# mbed-enablement-platform_F_1.net
KiCad netlist of a schematic drawn in Altium Designer
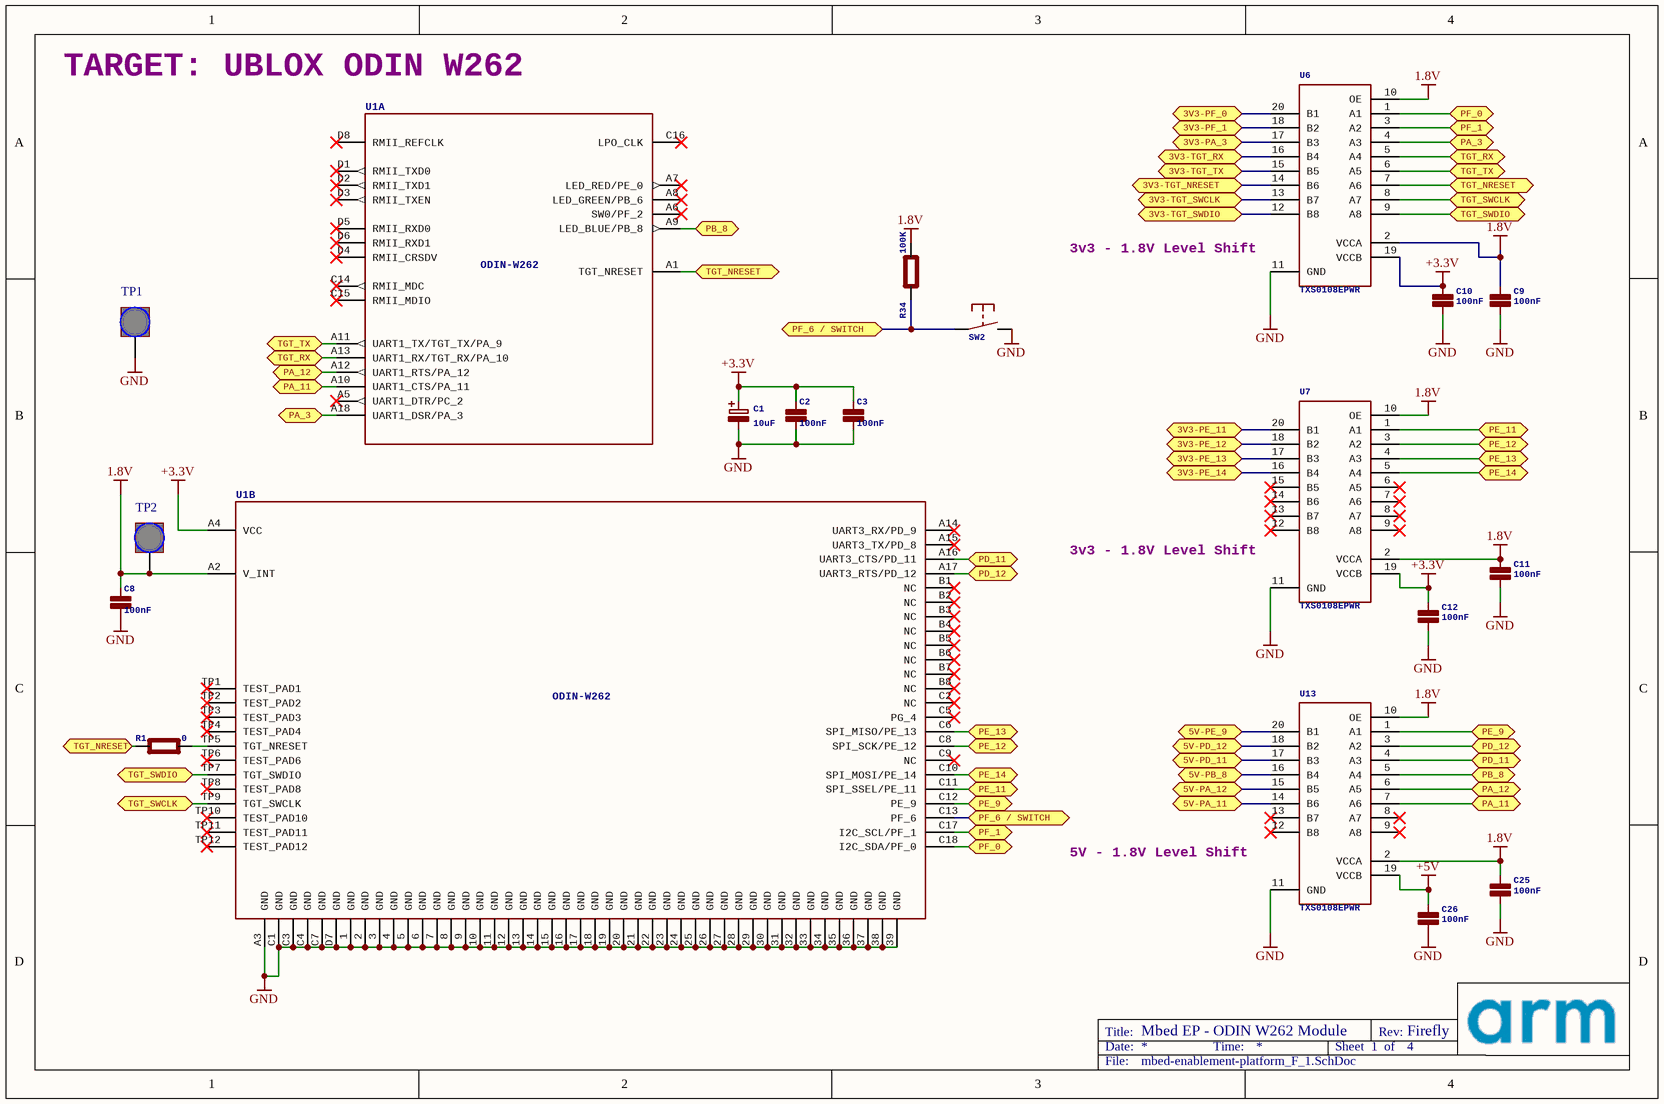
[diagram p0: mbed-enablement-platform_F_1.SchDoc]

(export (version "E")
  (design (tool "Eeschema 10.0.6"))
  (components
    (comp (ref "C1")
      (value "10uF")
      (footprint "SMC_B")
      (description "Polarised capacitor")
      (fields (field (name "MF") "Kemet"))
      (libsource (lib "mbed-workplace-env-mon") (part "CAPACITOR-POLARISEDB"))
    )
    (comp (ref "C2")
      (value "100nF")
      (footprint "0603")
      (description "Capacitor")
      (libsource (lib "mbed-workplace-env-mon") (part "CAPACITOR0603"))
    )
    (comp (ref "C3")
      (value "100nF")
      (footprint "0603")
      (description "Capacitor")
      (libsource (lib "mbed-workplace-env-mon") (part "CAPACITOR0603"))
    )
    (comp (ref "C8")
      (value "100nF")
      (footprint "0603")
      (description "Capacitor")
      (libsource (lib "mbed-workplace-env-mon") (part "CAPACITOR0603"))
    )
    (comp (ref "C9")
      (value "100nF")
      (footprint "0603")
      (description "Capacitor")
      (libsource (lib "mbed-workplace-env-mon") (part "CAPACITOR0603"))
    )
    (comp (ref "C10")
      (value "100nF")
      (footprint "0603")
      (description "Capacitor")
      (libsource (lib "mbed-workplace-env-mon") (part "CAPACITOR0603"))
    )
    (comp (ref "C11")
      (value "100nF")
      (footprint "0603")
      (description "Capacitor")
      (libsource (lib "mbed-workplace-env-mon") (part "CAPACITOR0603"))
    )
    (comp (ref "C12")
      (value "100nF")
      (footprint "0603")
      (description "Capacitor")
      (libsource (lib "mbed-workplace-env-mon") (part "CAPACITOR0603"))
    )
    (comp (ref "C25")
      (value "100nF")
      (footprint "0603")
      (description "Capacitor")
      (libsource (lib "mbed-workplace-env-mon") (part "CAPACITOR0603"))
    )
    (comp (ref "C26")
      (value "100nF")
      (footprint "0603")
      (description "Capacitor")
      (libsource (lib "mbed-workplace-env-mon") (part "CAPACITOR0603"))
    )
    (comp (ref "R1")
      (value "0")
      (footprint "0402")
      (description "Resistor")
      (libsource (lib "mbed-workplace-env-mon") (part "RESISTOR0402"))
    )
    (comp (ref "R34")
      (value "100K")
      (footprint "0402")
      (description "Resistor")
      (libsource (lib "mbed-workplace-env-mon") (part "RESISTOR0402"))
    )
    (comp (ref "SW2")
      (value "MOMENTARY SWITCH RA (SPST)")
      (footprint "EVQ-PF006K")
      (description "EVQ-PF006K")
      (fields (field (name "MF") "Panasonic"))
      (libsource (lib "mbed-workplace-env-mon") (part "EVQ-PF006K"))
    )
    (comp (ref "TP1")
      (value "TP, 1.5mm")
      (footprint "TP1.5")
      (description "1.5mm round test point")
      (libsource (lib "mbed-workplace-env-mon") (part "TP1.5"))
    )
    (comp (ref "TP2")
      (value "TP, 1.5mm")
      (footprint "TP1.5")
      (description "1.5mm round test point")
      (libsource (lib "") (part "TP1.5_1"))
    )
    (comp (ref "U1")
      (value "ODIN-W262")
      (footprint "ODIN-88")
      (description "ODIN-W260: Host-based multiradio module with Wi-Fi and Bluetooth, internal antenna   u-blox.com")
      (libsource (lib "mbed-workplace-env-mon") (part "ODIN-W262"))
    )
    (comp (ref "U6")
      (value "TXS0108EPWR")
      (footprint "TSSOP-20")
      (description "8-Bit Bi-directional, Level-Shifting, Voltage Translator")
      (fields (field (name "MF") "Texas Instruments"))
      (libsource (lib "mbed-workplace-env-mon") (part "TXS0108EPWR"))
    )
    (comp (ref "U7")
      (value "TXS0108EPWR")
      (footprint "TSSOP-20")
      (description "8-Bit Bi-directional, Level-Shifting, Voltage Translator")
      (fields (field (name "MF") "Texas Instruments"))
      (libsource (lib "mbed-workplace-env-mon") (part "TXS0108EPWR"))
    )
    (comp (ref "U13")
      (value "TXS0108EPWR")
      (footprint "TSSOP-20")
      (description "8-Bit Bi-directional, Level-Shifting, Voltage Translator")
      (fields (field (name "MF") "Texas Instruments"))
      (libsource (lib "mbed-workplace-env-mon") (part "TXS0108EPWR"))
    )
  )
  (nets
    (net (code "1") (name "+3.3V") (class "Default")
      (node (ref "C1") (pin "+") (pinfunction "+_+") (pintype "passive"))
      (node (ref "C10") (pin "1") (pinfunction "P$1_1") (pintype "passive"))
      (node (ref "C12") (pin "1") (pinfunction "P$1_1") (pintype "passive"))
      (node (ref "C2") (pin "1") (pinfunction "P$1_1") (pintype "passive"))
      (node (ref "C3") (pin "1") (pinfunction "P$1_1") (pintype "passive"))
      (node (ref "U1") (pin "A4") (pinfunction "VCC_A4") (pintype "power_in"))
      (node (ref "U6") (pin "19") (pinfunction "VCCB_19") (pintype "passive"))
      (node (ref "U7") (pin "19") (pinfunction "VCCB_19") (pintype "passive"))
    )
    (net (code "2") (name "+5V") (class "Default")
      (node (ref "C26") (pin "1") (pinfunction "P$1_1") (pintype "passive"))
      (node (ref "U13") (pin "19") (pinfunction "VCCB_19") (pintype "passive"))
    )
    (net (code "3") (name "/3V3-PA_3") (class "Default")
      (node (ref "U6") (pin "17") (pinfunction "B3_17") (pintype "passive"))
    )
    (net (code "4") (name "/3V3-PE_11") (class "Default")
      (node (ref "U7") (pin "20") (pinfunction "B1_20") (pintype "passive"))
    )
    (net (code "5") (name "/3V3-PE_12") (class "Default")
      (node (ref "U7") (pin "18") (pinfunction "B2_18") (pintype "passive"))
    )
    (net (code "6") (name "/3V3-PE_13") (class "Default")
      (node (ref "U7") (pin "17") (pinfunction "B3_17") (pintype "passive"))
    )
    (net (code "7") (name "/3V3-PE_14") (class "Default")
      (node (ref "U7") (pin "16") (pinfunction "B4_16") (pintype "passive"))
    )
    (net (code "8") (name "/3V3-PF_0") (class "Default")
      (node (ref "U6") (pin "20") (pinfunction "B1_20") (pintype "passive"))
    )
    (net (code "9") (name "/3V3-PF_1") (class "Default")
      (node (ref "U6") (pin "18") (pinfunction "B2_18") (pintype "passive"))
    )
    (net (code "10") (name "/3V3-TGT_NRESET") (class "Default")
      (node (ref "U6") (pin "14") (pinfunction "B6_14") (pintype "passive"))
    )
    (net (code "11") (name "/3V3-TGT_RX") (class "Default")
      (node (ref "U6") (pin "16") (pinfunction "B4_16") (pintype "passive"))
    )
    (net (code "12") (name "/3V3-TGT_SWCLK") (class "Default")
      (node (ref "U6") (pin "13") (pinfunction "B7_13") (pintype "passive"))
    )
    (net (code "13") (name "/3V3-TGT_SWDIO") (class "Default")
      (node (ref "U6") (pin "12") (pinfunction "B8_12") (pintype "passive"))
    )
    (net (code "14") (name "/3V3-TGT_TX") (class "Default")
      (node (ref "U6") (pin "15") (pinfunction "B5_15") (pintype "passive"))
    )
    (net (code "15") (name "/5V-PA_11") (class "Default")
      (node (ref "U13") (pin "14") (pinfunction "B6_14") (pintype "passive"))
    )
    (net (code "16") (name "/5V-PA_12") (class "Default")
      (node (ref "U13") (pin "15") (pinfunction "B5_15") (pintype "passive"))
    )
    (net (code "17") (name "/5V-PB_8") (class "Default")
      (node (ref "U13") (pin "16") (pinfunction "B4_16") (pintype "passive"))
    )
    (net (code "18") (name "/5V-PD_11") (class "Default")
      (node (ref "U13") (pin "17") (pinfunction "B3_17") (pintype "passive"))
    )
    (net (code "19") (name "/5V-PD_12") (class "Default")
      (node (ref "U13") (pin "18") (pinfunction "B2_18") (pintype "passive"))
    )
    (net (code "20") (name "/5V-PE_9") (class "Default")
      (node (ref "U13") (pin "20") (pinfunction "B1_20") (pintype "passive"))
    )
    (net (code "21") (name "/PA_3") (class "Default")
      (node (ref "U1") (pin "A18") (pinfunction "UART1_DSR/PA_3_A18") (pintype "passive"))
      (node (ref "U6") (pin "4") (pinfunction "A3_4") (pintype "passive"))
    )
    (net (code "22") (name "/PA_11") (class "Default")
      (node (ref "U1") (pin "A10") (pinfunction "UART1_CTS/PA_11_A10") (pintype "passive"))
      (node (ref "U13") (pin "7") (pinfunction "A6_7") (pintype "passive"))
    )
    (net (code "23") (name "/PA_12") (class "Default")
      (node (ref "U1") (pin "A12") (pinfunction "UART1_RTS/PA_12_A12") (pintype "output"))
      (node (ref "U13") (pin "6") (pinfunction "A5_6") (pintype "passive"))
    )
    (net (code "24") (name "/PB_8") (class "Default")
      (node (ref "U1") (pin "A9") (pinfunction "LED_BLUE/PB_8_A9") (pintype "output"))
      (node (ref "U13") (pin "5") (pinfunction "A4_5") (pintype "passive"))
    )
    (net (code "25") (name "/PD_11") (class "Default")
      (node (ref "U1") (pin "A16") (pinfunction "UART3_CTS/PD_11_A16") (pintype "passive"))
      (node (ref "U13") (pin "4") (pinfunction "A3_4") (pintype "passive"))
    )
    (net (code "26") (name "/PD_12") (class "Default")
      (node (ref "U1") (pin "A17") (pinfunction "UART3_RTS/PD_12_A17") (pintype "passive"))
      (node (ref "U13") (pin "3") (pinfunction "A2_3") (pintype "passive"))
    )
    (net (code "27") (name "/PE_9") (class "Default")
      (node (ref "U1") (pin "C12") (pinfunction "PE_9_C12") (pintype "passive"))
      (node (ref "U13") (pin "1") (pinfunction "A1_1") (pintype "passive"))
    )
    (net (code "28") (name "/PE_11") (class "Default")
      (node (ref "U1") (pin "C11") (pinfunction "SPI_SSEL/PE_11_C11") (pintype "passive"))
      (node (ref "U7") (pin "1") (pinfunction "A1_1") (pintype "passive"))
    )
    (net (code "29") (name "/PE_12") (class "Default")
      (node (ref "U1") (pin "C8") (pinfunction "SPI_SCK/PE_12_C8") (pintype "passive"))
      (node (ref "U7") (pin "3") (pinfunction "A2_3") (pintype "passive"))
    )
    (net (code "30") (name "/PE_13") (class "Default")
      (node (ref "U1") (pin "C6") (pinfunction "SPI_MISO/PE_13_C6") (pintype "passive"))
      (node (ref "U7") (pin "4") (pinfunction "A3_4") (pintype "passive"))
    )
    (net (code "31") (name "/PE_14") (class "Default")
      (node (ref "U1") (pin "C10") (pinfunction "SPI_MOSI/PE_14_C10") (pintype "passive"))
      (node (ref "U7") (pin "5") (pinfunction "A4_5") (pintype "passive"))
    )
    (net (code "32") (name "/PF_0") (class "Default")
      (node (ref "U1") (pin "C18") (pinfunction "I2C_SDA/PF_0_C18") (pintype "passive"))
      (node (ref "U6") (pin "1") (pinfunction "A1_1") (pintype "passive"))
    )
    (net (code "33") (name "/PF_1") (class "Default")
      (node (ref "U1") (pin "C17") (pinfunction "I2C_SCL/PF_1_C17") (pintype "passive"))
      (node (ref "U6") (pin "3") (pinfunction "A2_3") (pintype "passive"))
    )
    (net (code "34") (name "/PF_6 {slash} SWITCH") (class "Default")
      (node (ref "R34") (pin "1") (pinfunction "P$1_1") (pintype "passive"))
      (node (ref "SW2") (pin "1") (pinfunction "1_1") (pintype "passive"))
      (node (ref "U1") (pin "C13") (pinfunction "PF_6_C13") (pintype "passive"))
    )
    (net (code "35") (name "/TGT_NRESET") (class "Default")
      (node (ref "R1") (pin "1") (pinfunction "P$1_1") (pintype "passive"))
      (node (ref "U1") (pin "A1") (pinfunction "TGT_NRESET_A1") (pintype "passive"))
      (node (ref "U6") (pin "7") (pinfunction "A6_7") (pintype "passive"))
    )
    (net (code "36") (name "/TGT_RX") (class "Default")
      (node (ref "U1") (pin "A13") (pinfunction "UART1_RX/TGT_RX/PA_10_A13") (pintype "passive"))
      (node (ref "U6") (pin "5") (pinfunction "A4_5") (pintype "passive"))
    )
    (net (code "37") (name "/TGT_SWCLK") (class "Default")
      (node (ref "U1") (pin "TP9") (pinfunction "TGT_SWCLK_TP9") (pintype "passive"))
      (node (ref "U6") (pin "8") (pinfunction "A7_8") (pintype "passive"))
    )
    (net (code "38") (name "/TGT_SWDIO") (class "Default")
      (node (ref "U1") (pin "TP7") (pinfunction "TGT_SWDIO_TP7") (pintype "passive"))
      (node (ref "U6") (pin "9") (pinfunction "A8_9") (pintype "passive"))
    )
    (net (code "39") (name "/TGT_TX") (class "Default")
      (node (ref "U1") (pin "A11") (pinfunction "UART1_TX/TGT_TX/PA_9_A11") (pintype "output"))
      (node (ref "U6") (pin "6") (pinfunction "A5_6") (pintype "passive"))
    )
    (net (code "40") (name "1.8V") (class "Default")
      (node (ref "C11") (pin "1") (pinfunction "P$1_1") (pintype "passive"))
      (node (ref "C25") (pin "1") (pinfunction "P$1_1") (pintype "passive"))
      (node (ref "C8") (pin "1") (pinfunction "P$1_1") (pintype "passive"))
      (node (ref "C9") (pin "1") (pinfunction "P$1_1") (pintype "passive"))
      (node (ref "R34") (pin "2") (pinfunction "P$2_2") (pintype "passive"))
      (node (ref "TP2") (pin "1") (pinfunction "1_1") (pintype "passive"))
      (node (ref "U1") (pin "A2") (pinfunction "V_INT_A2") (pintype "power_in"))
      (node (ref "U13") (pin "10") (pinfunction "OE_10") (pintype "passive"))
      (node (ref "U13") (pin "2") (pinfunction "VCCA_2") (pintype "passive"))
      (node (ref "U6") (pin "10") (pinfunction "OE_10") (pintype "passive"))
      (node (ref "U6") (pin "2") (pinfunction "VCCA_2") (pintype "passive"))
      (node (ref "U7") (pin "10") (pinfunction "OE_10") (pintype "passive"))
      (node (ref "U7") (pin "2") (pinfunction "VCCA_2") (pintype "passive"))
    )
    (net (code "41") (name "GND") (class "Default")
      (node (ref "C1") (pin "-") (pinfunction "-_-") (pintype "passive"))
      (node (ref "C10") (pin "2") (pinfunction "P$2_2") (pintype "passive"))
      (node (ref "C11") (pin "2") (pinfunction "P$2_2") (pintype "passive"))
      (node (ref "C12") (pin "2") (pinfunction "P$2_2") (pintype "passive"))
      (node (ref "C2") (pin "2") (pinfunction "P$2_2") (pintype "passive"))
      (node (ref "C25") (pin "2") (pinfunction "P$2_2") (pintype "passive"))
      (node (ref "C26") (pin "2") (pinfunction "P$2_2") (pintype "passive"))
      (node (ref "C3") (pin "2") (pinfunction "P$2_2") (pintype "passive"))
      (node (ref "C8") (pin "2") (pinfunction "P$2_2") (pintype "passive"))
      (node (ref "C9") (pin "2") (pinfunction "P$2_2") (pintype "passive"))
      (node (ref "SW2") (pin "2") (pinfunction "2_2") (pintype "passive"))
      (node (ref "TP1") (pin "1") (pinfunction "1_1") (pintype "passive"))
      (node (ref "U1") (pin "1") (pinfunction "GND_1") (pintype "power_in"))
      (node (ref "U1") (pin "10") (pinfunction "GND_10") (pintype "power_in"))
      (node (ref "U1") (pin "11") (pinfunction "GND_11") (pintype "power_in"))
      (node (ref "U1") (pin "12") (pinfunction "GND_12") (pintype "power_in"))
      (node (ref "U1") (pin "13") (pinfunction "GND_13") (pintype "power_in"))
      (node (ref "U1") (pin "14") (pinfunction "GND_14") (pintype "power_in"))
      (node (ref "U1") (pin "15") (pinfunction "GND_15") (pintype "power_in"))
      (node (ref "U1") (pin "16") (pinfunction "GND_16") (pintype "power_in"))
      (node (ref "U1") (pin "17") (pinfunction "GND_17") (pintype "power_in"))
      (node (ref "U1") (pin "18") (pinfunction "GND_18") (pintype "power_in"))
      (node (ref "U1") (pin "19") (pinfunction "GND_19") (pintype "power_in"))
      (node (ref "U1") (pin "2") (pinfunction "GND_2") (pintype "power_in"))
      (node (ref "U1") (pin "20") (pinfunction "GND_20") (pintype "power_in"))
      (node (ref "U1") (pin "21") (pinfunction "GND_21") (pintype "power_in"))
      (node (ref "U1") (pin "22") (pinfunction "GND_22") (pintype "power_in"))
      (node (ref "U1") (pin "23") (pinfunction "GND_23") (pintype "power_in"))
      (node (ref "U1") (pin "24") (pinfunction "GND_24") (pintype "power_in"))
      (node (ref "U1") (pin "25") (pinfunction "GND_25") (pintype "power_in"))
      (node (ref "U1") (pin "26") (pinfunction "GND_26") (pintype "power_in"))
      (node (ref "U1") (pin "27") (pinfunction "GND_27") (pintype "power_in"))
      (node (ref "U1") (pin "28") (pinfunction "GND_28") (pintype "power_in"))
      (node (ref "U1") (pin "29") (pinfunction "GND_29") (pintype "power_in"))
      (node (ref "U1") (pin "3") (pinfunction "GND_3") (pintype "power_in"))
      (node (ref "U1") (pin "30") (pinfunction "GND_30") (pintype "power_in"))
      (node (ref "U1") (pin "31") (pinfunction "GND_31") (pintype "power_in"))
      (node (ref "U1") (pin "32") (pinfunction "GND_32") (pintype "power_in"))
      (node (ref "U1") (pin "33") (pinfunction "GND_33") (pintype "power_in"))
      (node (ref "U1") (pin "34") (pinfunction "GND_34") (pintype "power_in"))
      (node (ref "U1") (pin "35") (pinfunction "GND_35") (pintype "power_in"))
      (node (ref "U1") (pin "36") (pinfunction "GND_36") (pintype "power_in"))
      (node (ref "U1") (pin "37") (pinfunction "GND_37") (pintype "power_in"))
      (node (ref "U1") (pin "38") (pinfunction "GND_38") (pintype "power_in"))
      (node (ref "U1") (pin "39") (pinfunction "GND_39") (pintype "power_in"))
      (node (ref "U1") (pin "4") (pinfunction "GND_4") (pintype "power_in"))
      (node (ref "U1") (pin "5") (pinfunction "GND_5") (pintype "power_in"))
      (node (ref "U1") (pin "6") (pinfunction "GND_6") (pintype "power_in"))
      (node (ref "U1") (pin "7") (pinfunction "GND_7") (pintype "power_in"))
      (node (ref "U1") (pin "8") (pinfunction "GND_8") (pintype "power_in"))
      (node (ref "U1") (pin "9") (pinfunction "GND_9") (pintype "power_in"))
      (node (ref "U1") (pin "A3") (pinfunction "GND_A3") (pintype "power_in"))
      (node (ref "U1") (pin "C1") (pinfunction "GND_C1") (pintype "power_in"))
      (node (ref "U1") (pin "C3") (pinfunction "GND_C3") (pintype "power_in"))
      (node (ref "U1") (pin "C4") (pinfunction "GND_C4") (pintype "power_in"))
      (node (ref "U1") (pin "C7") (pinfunction "GND_C7") (pintype "power_in"))
      (node (ref "U1") (pin "D7") (pinfunction "GND_D7") (pintype "power_in"))
      (node (ref "U13") (pin "11") (pinfunction "GND_11") (pintype "passive"))
      (node (ref "U6") (pin "11") (pinfunction "GND_11") (pintype "passive"))
      (node (ref "U7") (pin "11") (pinfunction "GND_11") (pintype "passive"))
    )
    (net (code "42") (name "Net-(R1-P$2)") (class "Default")
      (node (ref "R1") (pin "2") (pinfunction "P$2_2") (pintype "passive"))
      (node (ref "U1") (pin "TP5") (pinfunction "TGT_NRESET_TP5") (pintype "passive"))
    )
    (net (code "43") (name "unconnected-(U1A-LED_GREEN{slash}PB_6-PadA8)") (class "Default")
      (node (ref "U1") (pin "A8") (pinfunction "LED_GREEN/PB_6_A8") (pintype "passive+no_connect"))
    )
    (net (code "44") (name "unconnected-(U1A-LED_RED{slash}PE_0-PadA7)") (class "Default")
      (node (ref "U1") (pin "A7") (pinfunction "LED_RED/PE_0_A7") (pintype "output+no_connect"))
    )
    (net (code "45") (name "unconnected-(U1A-LPO_CLK-PadC16)") (class "Default")
      (node (ref "U1") (pin "C16") (pinfunction "LPO_CLK_C16") (pintype "passive+no_connect"))
    )
    (net (code "46") (name "unconnected-(U1A-RMII_CRSDV-PadD4)") (class "Default")
      (node (ref "U1") (pin "D4") (pinfunction "RMII_CRSDV_D4") (pintype "passive+no_connect"))
    )
    (net (code "47") (name "unconnected-(U1A-RMII_MDC-PadC14)") (class "Default")
      (node (ref "U1") (pin "C14") (pinfunction "RMII_MDC_C14") (pintype "output+no_connect"))
    )
    (net (code "48") (name "unconnected-(U1A-RMII_MDIO-PadC15)") (class "Default")
      (node (ref "U1") (pin "C15") (pinfunction "RMII_MDIO_C15") (pintype "passive+no_connect"))
    )
    (net (code "49") (name "unconnected-(U1A-RMII_REFCLK-PadD8)") (class "Default")
      (node (ref "U1") (pin "D8") (pinfunction "RMII_REFCLK_D8") (pintype "passive+no_connect"))
    )
    (net (code "50") (name "unconnected-(U1A-RMII_RXD0-PadD5)") (class "Default")
      (node (ref "U1") (pin "D5") (pinfunction "RMII_RXD0_D5") (pintype "passive+no_connect"))
    )
    (net (code "51") (name "unconnected-(U1A-RMII_RXD1-PadD6)") (class "Default")
      (node (ref "U1") (pin "D6") (pinfunction "RMII_RXD1_D6") (pintype "passive+no_connect"))
    )
    (net (code "52") (name "unconnected-(U1A-RMII_TXD0-PadD1)") (class "Default")
      (node (ref "U1") (pin "D1") (pinfunction "RMII_TXD0_D1") (pintype "output+no_connect"))
    )
    (net (code "53") (name "unconnected-(U1A-RMII_TXD1-PadD2)") (class "Default")
      (node (ref "U1") (pin "D2") (pinfunction "RMII_TXD1_D2") (pintype "output+no_connect"))
    )
    (net (code "54") (name "unconnected-(U1A-RMII_TXEN-PadD3)") (class "Default")
      (node (ref "U1") (pin "D3") (pinfunction "RMII_TXEN_D3") (pintype "output+no_connect"))
    )
    (net (code "55") (name "unconnected-(U1A-SW0{slash}PF_2-PadA6)") (class "Default")
      (node (ref "U1") (pin "A6") (pinfunction "SW0/PF_2_A6") (pintype "passive+no_connect"))
    )
    (net (code "56") (name "unconnected-(U1A-UART1_DTR{slash}PC_2-PadA5)") (class "Default")
      (node (ref "U1") (pin "A5") (pinfunction "UART1_DTR/PC_2_A5") (pintype "output+no_connect"))
    )
    (net (code "57") (name "unconnected-(U1B-NC-PadB1)") (class "Default")
      (node (ref "U1") (pin "B1") (pinfunction "NC_B1") (pintype "passive+no_connect"))
    )
    (net (code "58") (name "unconnected-(U1B-NC-PadB2)") (class "Default")
      (node (ref "U1") (pin "B2") (pinfunction "NC_B2") (pintype "passive+no_connect"))
    )
    (net (code "59") (name "unconnected-(U1B-NC-PadB3)") (class "Default")
      (node (ref "U1") (pin "B3") (pinfunction "NC_B3") (pintype "passive+no_connect"))
    )
    (net (code "60") (name "unconnected-(U1B-NC-PadB4)") (class "Default")
      (node (ref "U1") (pin "B4") (pinfunction "NC_B4") (pintype "passive+no_connect"))
    )
    (net (code "61") (name "unconnected-(U1B-NC-PadB5)") (class "Default")
      (node (ref "U1") (pin "B5") (pinfunction "NC_B5") (pintype "passive+no_connect"))
    )
    (net (code "62") (name "unconnected-(U1B-NC-PadB6)") (class "Default")
      (node (ref "U1") (pin "B6") (pinfunction "NC_B6") (pintype "passive+no_connect"))
    )
    (net (code "63") (name "unconnected-(U1B-NC-PadB7)") (class "Default")
      (node (ref "U1") (pin "B7") (pinfunction "NC_B7") (pintype "passive+no_connect"))
    )
    (net (code "64") (name "unconnected-(U1B-NC-PadB8)") (class "Default")
      (node (ref "U1") (pin "B8") (pinfunction "NC_B8") (pintype "passive+no_connect"))
    )
    (net (code "65") (name "unconnected-(U1B-NC-PadC2)") (class "Default")
      (node (ref "U1") (pin "C2") (pinfunction "NC_C2") (pintype "passive+no_connect"))
    )
    (net (code "66") (name "unconnected-(U1B-NC-PadC9)") (class "Default")
      (node (ref "U1") (pin "C9") (pinfunction "NC_C9") (pintype "passive+no_connect"))
    )
    (net (code "67") (name "unconnected-(U1B-PG_4-PadC5)") (class "Default")
      (node (ref "U1") (pin "C5") (pinfunction "PG_4_C5") (pintype "passive+no_connect"))
    )
    (net (code "68") (name "unconnected-(U1B-TEST_PAD1-PadTP1)") (class "Default")
      (node (ref "U1") (pin "TP1") (pinfunction "TEST_PAD1_TP1") (pintype "passive+no_connect"))
    )
    (net (code "69") (name "unconnected-(U1B-TEST_PAD2-PadTP2)") (class "Default")
      (node (ref "U1") (pin "TP2") (pinfunction "TEST_PAD2_TP2") (pintype "passive+no_connect"))
    )
    (net (code "70") (name "unconnected-(U1B-TEST_PAD3-PadTP3)") (class "Default")
      (node (ref "U1") (pin "TP3") (pinfunction "TEST_PAD3_TP3") (pintype "passive+no_connect"))
    )
    (net (code "71") (name "unconnected-(U1B-TEST_PAD4-PadTP4)") (class "Default")
      (node (ref "U1") (pin "TP4") (pinfunction "TEST_PAD4_TP4") (pintype "passive+no_connect"))
    )
    (net (code "72") (name "unconnected-(U1B-TEST_PAD6-PadTP6)") (class "Default")
      (node (ref "U1") (pin "TP6") (pinfunction "TEST_PAD6_TP6") (pintype "passive+no_connect"))
    )
    (net (code "73") (name "unconnected-(U1B-TEST_PAD8-PadTP8)") (class "Default")
      (node (ref "U1") (pin "TP8") (pinfunction "TEST_PAD8_TP8") (pintype "passive+no_connect"))
    )
    (net (code "74") (name "unconnected-(U1B-TEST_PAD10-PadTP10)") (class "Default")
      (node (ref "U1") (pin "TP10") (pinfunction "TEST_PAD10_TP10") (pintype "passive+no_connect"))
    )
    (net (code "75") (name "unconnected-(U1B-TEST_PAD11-PadTP11)") (class "Default")
      (node (ref "U1") (pin "TP11") (pinfunction "TEST_PAD11_TP11") (pintype "passive+no_connect"))
    )
    (net (code "76") (name "unconnected-(U1B-TEST_PAD12-PadTP12)") (class "Default")
      (node (ref "U1") (pin "TP12") (pinfunction "TEST_PAD12_TP12") (pintype "passive+no_connect"))
    )
    (net (code "77") (name "unconnected-(U1B-UART3_RX{slash}PD_9-PadA14)") (class "Default")
      (node (ref "U1") (pin "A14") (pinfunction "UART3_RX/PD_9_A14") (pintype "passive+no_connect"))
    )
    (net (code "78") (name "unconnected-(U1B-UART3_TX{slash}PD_8-PadA15)") (class "Default")
      (node (ref "U1") (pin "A15") (pinfunction "UART3_TX/PD_8_A15") (pintype "passive+no_connect"))
    )
    (net (code "79") (name "unconnected-(U7-A5-Pad6)") (class "Default")
      (node (ref "U7") (pin "6") (pinfunction "A5_6") (pintype "passive+no_connect"))
    )
    (net (code "80") (name "unconnected-(U7-A6-Pad7)") (class "Default")
      (node (ref "U7") (pin "7") (pinfunction "A6_7") (pintype "passive+no_connect"))
    )
    (net (code "81") (name "unconnected-(U7-A7-Pad8)") (class "Default")
      (node (ref "U7") (pin "8") (pinfunction "A7_8") (pintype "passive+no_connect"))
    )
    (net (code "82") (name "unconnected-(U7-A8-Pad9)") (class "Default")
      (node (ref "U7") (pin "9") (pinfunction "A8_9") (pintype "passive+no_connect"))
    )
    (net (code "83") (name "unconnected-(U7-B5-Pad15)") (class "Default")
      (node (ref "U7") (pin "15") (pinfunction "B5_15") (pintype "passive+no_connect"))
    )
    (net (code "84") (name "unconnected-(U7-B6-Pad14)") (class "Default")
      (node (ref "U7") (pin "14") (pinfunction "B6_14") (pintype "passive+no_connect"))
    )
    (net (code "85") (name "unconnected-(U7-B7-Pad13)") (class "Default")
      (node (ref "U7") (pin "13") (pinfunction "B7_13") (pintype "passive+no_connect"))
    )
    (net (code "86") (name "unconnected-(U7-B8-Pad12)") (class "Default")
      (node (ref "U7") (pin "12") (pinfunction "B8_12") (pintype "passive+no_connect"))
    )
    (net (code "87") (name "unconnected-(U13-A7-Pad8)") (class "Default")
      (node (ref "U13") (pin "8") (pinfunction "A7_8") (pintype "passive+no_connect"))
    )
    (net (code "88") (name "unconnected-(U13-A8-Pad9)") (class "Default")
      (node (ref "U13") (pin "9") (pinfunction "A8_9") (pintype "passive+no_connect"))
    )
    (net (code "89") (name "unconnected-(U13-B7-Pad13)") (class "Default")
      (node (ref "U13") (pin "13") (pinfunction "B7_13") (pintype "passive+no_connect"))
    )
    (net (code "90") (name "unconnected-(U13-B8-Pad12)") (class "Default")
      (node (ref "U13") (pin "12") (pinfunction "B8_12") (pintype "passive+no_connect"))
    )
  )
)
